# volume1882.net
KiCad netlist of a schematic drawn in EAGLE
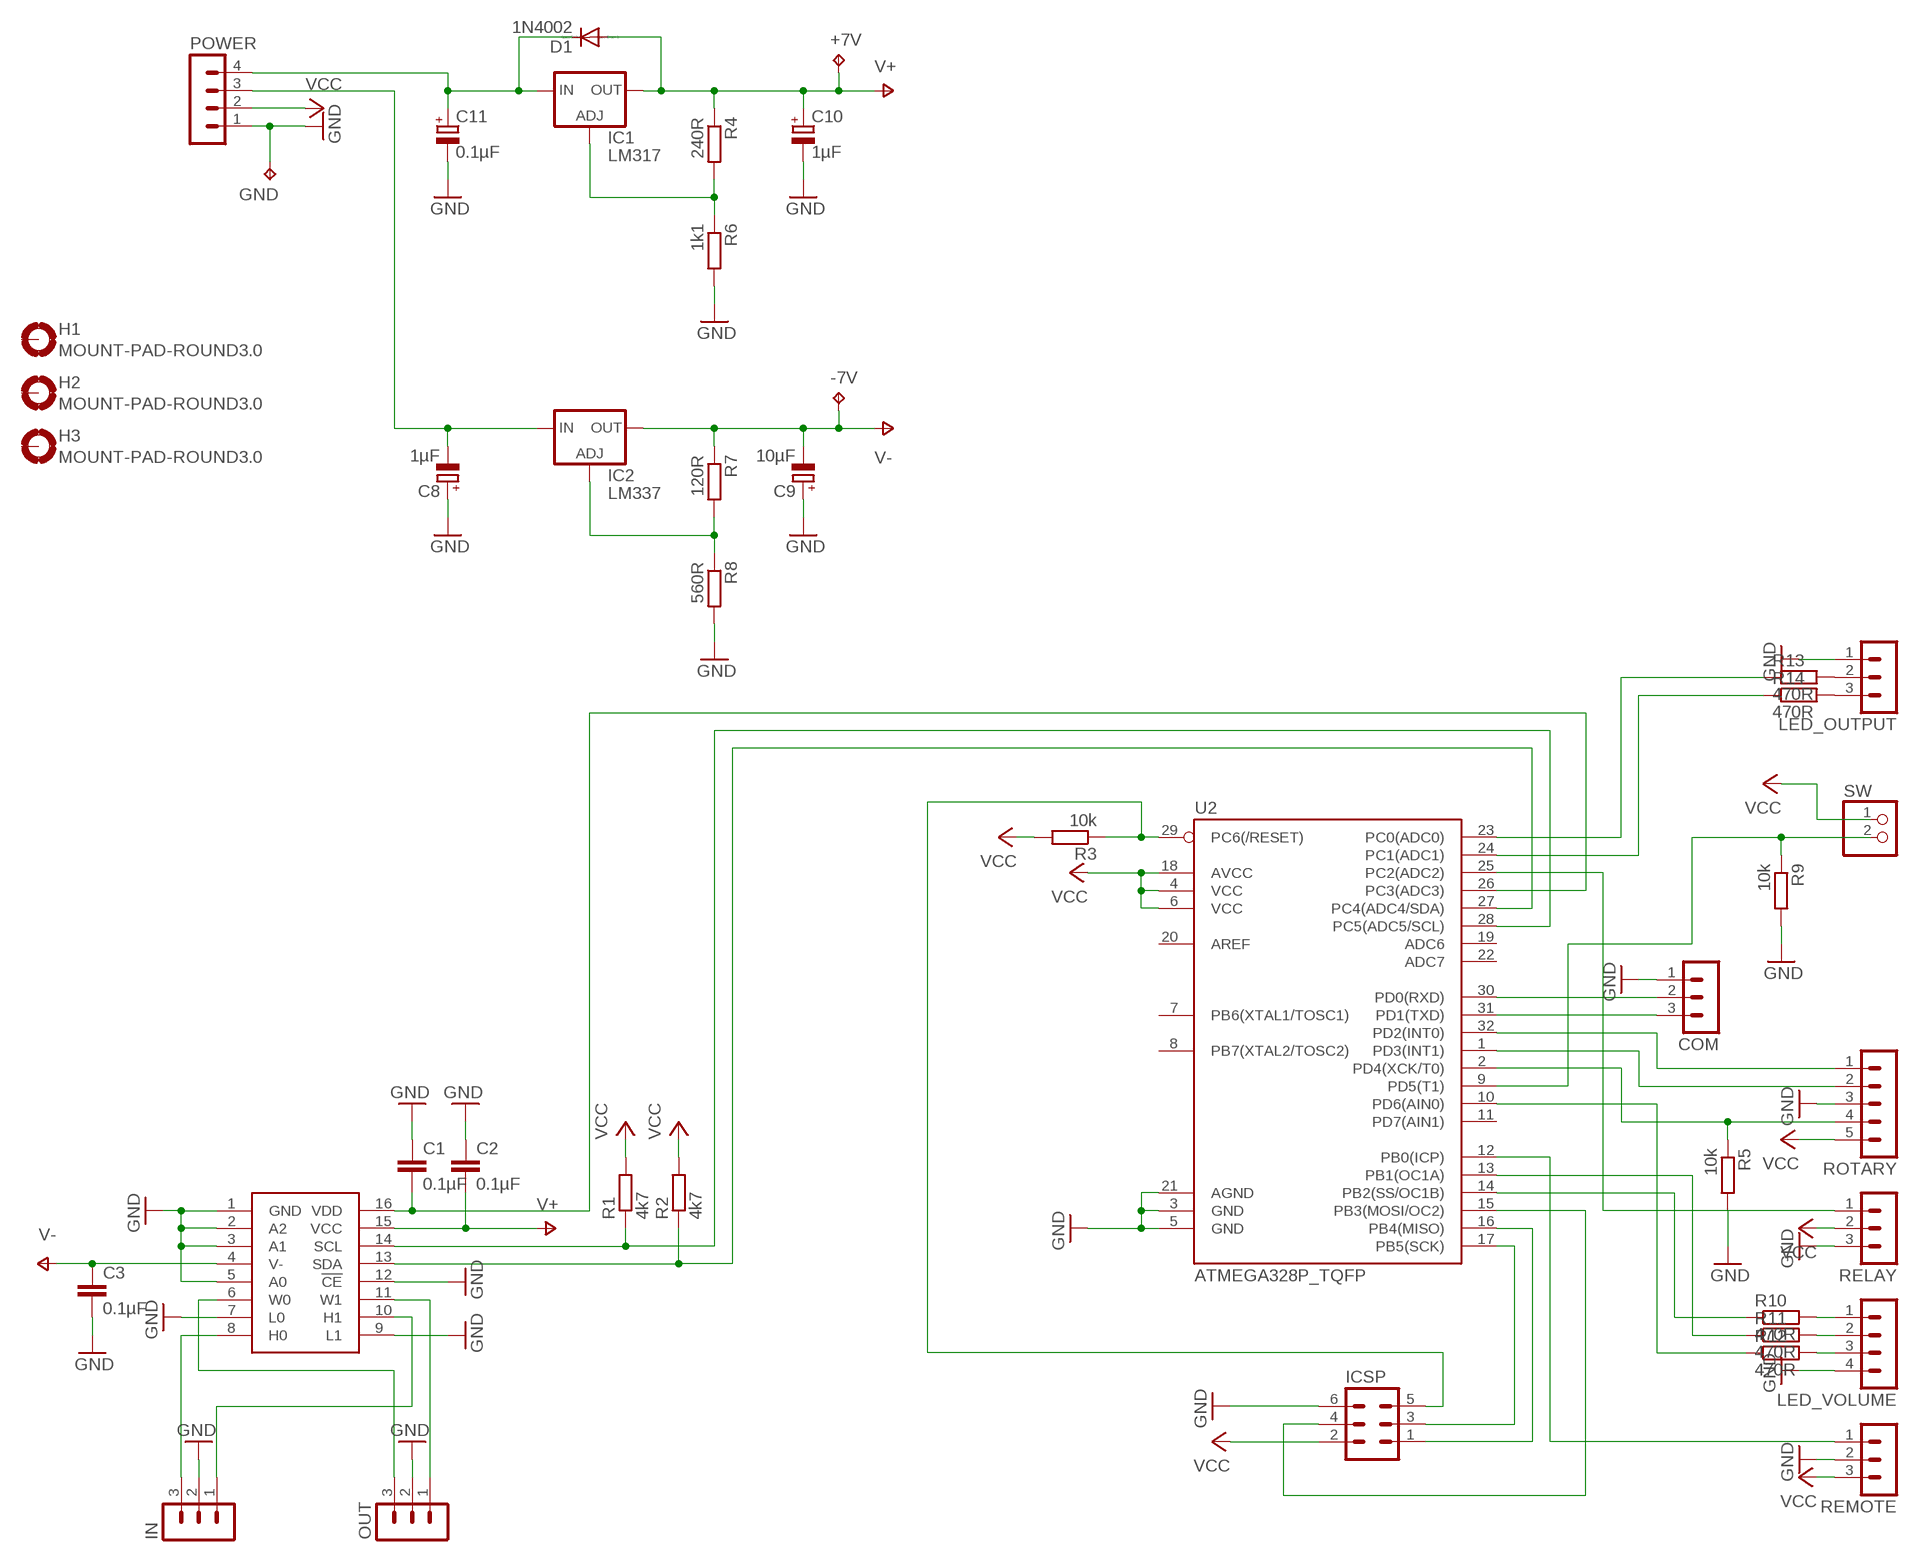
[diagram p0: schematic, sheet 1]

(export (version "E")
  (design (tool "Eeschema 10.0.6"))
  (components
    (comp (ref "+7V")
      (value "TPTP12SQ")
      (footprint "eagle-import:TP12SQ")
      (libsource (lib "eagle-import") (part "TPTP12SQ"))
    )
    (comp (ref "-7V")
      (value "TPTP12SQ")
      (footprint "eagle-import:TP12SQ")
      (libsource (lib "eagle-import") (part "TPTP12SQ"))
    )
    (comp (ref "C1")
      (value "0.1µF")
      (footprint "eagle-import:C1206")
      (libsource (lib "eagle-import") (part "C-EUC1206"))
    )
    (comp (ref "C2")
      (value "0.1µF")
      (footprint "eagle-import:C1206")
      (libsource (lib "eagle-import") (part "C-EUC1206"))
    )
    (comp (ref "C3")
      (value "0.1µF")
      (footprint "eagle-import:C1206")
      (libsource (lib "eagle-import") (part "C-EUC1206"))
    )
    (comp (ref "C8")
      (value "1µF")
      (footprint "eagle-import:E2-5")
      (libsource (lib "eagle-import") (part "CPOL-EUE2-5"))
    )
    (comp (ref "C9")
      (value "10µF")
      (footprint "eagle-import:E2-5")
      (libsource (lib "eagle-import") (part "CPOL-EUE2-5"))
    )
    (comp (ref "C10")
      (value "1µF")
      (footprint "eagle-import:E2-5")
      (libsource (lib "eagle-import") (part "CPOL-EUE2-5"))
    )
    (comp (ref "C11")
      (value "0.1µF")
      (footprint "eagle-import:E2-5")
      (libsource (lib "eagle-import") (part "CPOL-EUE2-5"))
    )
    (comp (ref "COM")
      (value "MA03-1")
      (footprint "eagle-import:MA03-1")
      (libsource (lib "eagle-import") (part "MA03-1"))
    )
    (comp (ref "D1")
      (value "1N4002")
      (footprint "eagle-import:DO41-10")
      (libsource (lib "eagle-import") (part "1N4004"))
    )
    (comp (ref "GND")
      (value "TPTP12SQ")
      (footprint "eagle-import:TP12SQ")
      (libsource (lib "eagle-import") (part "TPTP12SQ"))
    )
    (comp (ref "H1")
      (value "MOUNT-PAD-ROUND3.0")
      (footprint "eagle-import:3,0-PAD")
      (libsource (lib "eagle-import") (part "MOUNT-PAD-ROUND3.0"))
    )
    (comp (ref "H2")
      (value "MOUNT-PAD-ROUND3.0")
      (footprint "eagle-import:3,0-PAD")
      (libsource (lib "eagle-import") (part "MOUNT-PAD-ROUND3.0"))
    )
    (comp (ref "H3")
      (value "MOUNT-PAD-ROUND3.0")
      (footprint "eagle-import:3,0-PAD")
      (libsource (lib "eagle-import") (part "MOUNT-PAD-ROUND3.0"))
    )
    (comp (ref "IC1")
      (value "LM317")
      (footprint "eagle-import:SOT223")
      (libsource (lib "eagle-import") (part "LM317?MBSTT3"))
    )
    (comp (ref "IC2")
      (value "LM337")
      (footprint "eagle-import:SOT223")
      (libsource (lib "eagle-import") (part "LM337"))
    )
    (comp (ref "ICSP")
      (value "MA03-2")
      (footprint "eagle-import:MA03-2")
      (libsource (lib "eagle-import") (part "MA03-2"))
    )
    (comp (ref "IN")
      (value "MA03-1")
      (footprint "eagle-import:MA03-1")
      (libsource (lib "eagle-import") (part "MA03-1"))
    )
    (comp (ref "LED_OUTPUT")
      (value "MA03-1")
      (footprint "eagle-import:MA03-1")
      (libsource (lib "eagle-import") (part "MA03-1"))
    )
    (comp (ref "LED_VOLUME")
      (value "MA04-1")
      (footprint "eagle-import:MA04-1")
      (libsource (lib "eagle-import") (part "MA04-1"))
    )
    (comp (ref "OUT")
      (value "MA03-1")
      (footprint "eagle-import:MA03-1")
      (libsource (lib "eagle-import") (part "MA03-1"))
    )
    (comp (ref "POWER")
      (value "MA04-1")
      (footprint "eagle-import:MA04-1")
      (libsource (lib "eagle-import") (part "MA04-1"))
    )
    (comp (ref "R1")
      (value "4k7")
      (footprint "eagle-import:R1206")
      (libsource (lib "eagle-import") (part "R-EU_R1206"))
    )
    (comp (ref "R2")
      (value "4k7")
      (footprint "eagle-import:R1206")
      (libsource (lib "eagle-import") (part "R-EU_R1206"))
    )
    (comp (ref "R3")
      (value "10k")
      (footprint "eagle-import:R1206")
      (libsource (lib "eagle-import") (part "R-EU_R1206"))
    )
    (comp (ref "R4")
      (value "240R")
      (footprint "eagle-import:R1206")
      (libsource (lib "eagle-import") (part "R-EU_R1206"))
    )
    (comp (ref "R5")
      (value "10k")
      (footprint "eagle-import:R1206")
      (libsource (lib "eagle-import") (part "R-EU_R1206"))
    )
    (comp (ref "R6")
      (value "1k1")
      (footprint "eagle-import:R1206")
      (libsource (lib "eagle-import") (part "R-EU_R1206"))
    )
    (comp (ref "R7")
      (value "120R")
      (footprint "eagle-import:R1206")
      (libsource (lib "eagle-import") (part "R-EU_R1206"))
    )
    (comp (ref "R8")
      (value "560R")
      (footprint "eagle-import:R1206")
      (libsource (lib "eagle-import") (part "R-EU_R1206"))
    )
    (comp (ref "R9")
      (value "10k")
      (footprint "eagle-import:R1206")
      (libsource (lib "eagle-import") (part "R-EU_R1206"))
    )
    (comp (ref "R10")
      (value "470R")
      (footprint "eagle-import:R1206")
      (libsource (lib "eagle-import") (part "R-EU_R1206"))
    )
    (comp (ref "R11")
      (value "470R")
      (footprint "eagle-import:R1206")
      (libsource (lib "eagle-import") (part "R-EU_R1206"))
    )
    (comp (ref "R12")
      (value "470R")
      (footprint "eagle-import:R1206")
      (libsource (lib "eagle-import") (part "R-EU_R1206"))
    )
    (comp (ref "R13")
      (value "470R")
      (footprint "eagle-import:R1206")
      (libsource (lib "eagle-import") (part "R-EU_R1206"))
    )
    (comp (ref "R14")
      (value "470R")
      (footprint "eagle-import:R1206")
      (libsource (lib "eagle-import") (part "R-EU_R1206"))
    )
    (comp (ref "RELAY")
      (value "MA03-1")
      (footprint "eagle-import:MA03-1")
      (libsource (lib "eagle-import") (part "MA03-1"))
    )
    (comp (ref "REMOTE")
      (value "MA03-1")
      (footprint "eagle-import:MA03-1")
      (libsource (lib "eagle-import") (part "MA03-1"))
    )
    (comp (ref "ROTARY")
      (value "MA05-1")
      (footprint "eagle-import:MA05-1")
      (libsource (lib "eagle-import") (part "MA05-1"))
    )
    (comp (ref "SW")
      (value "PINHD-1X2")
      (footprint "eagle-import:1X02")
      (libsource (lib "eagle-import") (part "PINHD-1X2"))
    )
    (comp (ref "U1")
      (value "DS1882")
      (footprint "eagle-import:SO16")
      (libsource (lib "eagle-import") (part "DS1882"))
    )
    (comp (ref "U2")
      (value "ATMEGA328P_TQFP")
      (footprint "eagle-import:TQFP32-08")
      (libsource (lib "eagle-import") (part "ATMEGA328P_TQFP"))
    )
  )
  (nets
    (net (code "1") (name "GND") (class "Default")
      (node (ref "C1") (pin "1") (pinfunction "1_1") (pintype "passive"))
      (node (ref "C10") (pin "-") (pinfunction "-_-") (pintype "passive"))
      (node (ref "C11") (pin "-") (pinfunction "-_-") (pintype "passive"))
      (node (ref "C2") (pin "1") (pinfunction "1_1") (pintype "passive"))
      (node (ref "C3") (pin "2") (pinfunction "2_2") (pintype "passive"))
      (node (ref "C8") (pin "+") (pinfunction "+_+") (pintype "passive"))
      (node (ref "C9") (pin "+") (pinfunction "+_+") (pintype "passive"))
      (node (ref "COM") (pin "1") (pinfunction "1_1") (pintype "passive"))
      (node (ref "GND") (pin "TP") (pinfunction "TP_TP") (pintype "input"))
      (node (ref "ICSP") (pin "6") (pinfunction "6_6") (pintype "passive"))
      (node (ref "IN") (pin "2") (pinfunction "2_2") (pintype "passive"))
      (node (ref "LED_OUTPUT") (pin "1") (pinfunction "1_1") (pintype "passive"))
      (node (ref "LED_VOLUME") (pin "4") (pinfunction "4_4") (pintype "passive"))
      (node (ref "OUT") (pin "2") (pinfunction "2_2") (pintype "passive"))
      (node (ref "POWER") (pin "1") (pinfunction "1_1") (pintype "passive"))
      (node (ref "R5") (pin "2") (pinfunction "2_2") (pintype "passive"))
      (node (ref "R6") (pin "2") (pinfunction "2_2") (pintype "passive"))
      (node (ref "R8") (pin "2") (pinfunction "2_2") (pintype "passive"))
      (node (ref "R9") (pin "2") (pinfunction "2_2") (pintype "passive"))
      (node (ref "RELAY") (pin "3") (pinfunction "3_3") (pintype "passive"))
      (node (ref "REMOTE") (pin "2") (pinfunction "2_2") (pintype "passive"))
      (node (ref "ROTARY") (pin "3") (pinfunction "3_3") (pintype "passive"))
      (node (ref "U1") (pin "1") (pinfunction "GND_1") (pintype "power_in"))
      (node (ref "U1") (pin "12") (pinfunction "~{CE}_12") (pintype "bidirectional"))
      (node (ref "U1") (pin "2") (pinfunction "A2_2") (pintype "bidirectional"))
      (node (ref "U1") (pin "3") (pinfunction "A1_3") (pintype "bidirectional"))
      (node (ref "U1") (pin "5") (pinfunction "A0_5") (pintype "bidirectional"))
      (node (ref "U1") (pin "7") (pinfunction "L0_7") (pintype "bidirectional"))
      (node (ref "U1") (pin "9") (pinfunction "L1_9") (pintype "bidirectional"))
      (node (ref "U2") (pin "21") (pinfunction "AGND_21") (pintype "bidirectional"))
      (node (ref "U2") (pin "3") (pinfunction "GND_3") (pintype "bidirectional"))
      (node (ref "U2") (pin "5") (pinfunction "GND_5") (pintype "bidirectional"))
    )
    (net (code "2") (name "Net-(IC1-ADJ)") (class "Default")
      (node (ref "IC1") (pin "1") (pinfunction "ADJ_1") (pintype "input"))
      (node (ref "R4") (pin "2") (pinfunction "2_2") (pintype "passive"))
      (node (ref "R6") (pin "1") (pinfunction "1_1") (pintype "passive"))
    )
    (net (code "3") (name "Net-(IC1-IN)") (class "Default")
      (node (ref "C11") (pin "+") (pinfunction "+_+") (pintype "passive"))
      (node (ref "D1") (pin "C") (pinfunction "C_C") (pintype "passive"))
      (node (ref "IC1") (pin "3") (pinfunction "IN_3") (pintype "input"))
      (node (ref "POWER") (pin "4") (pinfunction "4_4") (pintype "passive"))
    )
    (net (code "4") (name "Net-(IC2-ADJ)") (class "Default")
      (node (ref "IC2") (pin "1") (pinfunction "ADJ_1") (pintype "input"))
      (node (ref "R7") (pin "2") (pinfunction "2_2") (pintype "passive"))
      (node (ref "R8") (pin "1") (pinfunction "1_1") (pintype "passive"))
    )
    (net (code "5") (name "Net-(IC2-IN)") (class "Default")
      (node (ref "C8") (pin "-") (pinfunction "-_-") (pintype "passive"))
      (node (ref "IC2") (pin "2") (pinfunction "IN_2") (pintype "input"))
      (node (ref "POWER") (pin "3") (pinfunction "3_3") (pintype "passive"))
    )
    (net (code "6") (name "Net-(LED_OUTPUT-Pad2)") (class "Default")
      (node (ref "LED_OUTPUT") (pin "2") (pinfunction "2_2") (pintype "passive"))
      (node (ref "R13") (pin "2") (pinfunction "2_2") (pintype "passive"))
    )
    (net (code "7") (name "Net-(LED_OUTPUT-Pad3)") (class "Default")
      (node (ref "LED_OUTPUT") (pin "3") (pinfunction "3_3") (pintype "passive"))
      (node (ref "R14") (pin "2") (pinfunction "2_2") (pintype "passive"))
    )
    (net (code "8") (name "Net-(LED_VOLUME-Pad1)") (class "Default")
      (node (ref "LED_VOLUME") (pin "1") (pinfunction "1_1") (pintype "passive"))
      (node (ref "R10") (pin "2") (pinfunction "2_2") (pintype "passive"))
    )
    (net (code "9") (name "Net-(LED_VOLUME-Pad2)") (class "Default")
      (node (ref "LED_VOLUME") (pin "2") (pinfunction "2_2") (pintype "passive"))
      (node (ref "R11") (pin "2") (pinfunction "2_2") (pintype "passive"))
    )
    (net (code "10") (name "Net-(LED_VOLUME-Pad3)") (class "Default")
      (node (ref "LED_VOLUME") (pin "3") (pinfunction "3_3") (pintype "passive"))
      (node (ref "R12") (pin "2") (pinfunction "2_2") (pintype "passive"))
    )
    (net (code "11") (name "Net-(U1-H0)") (class "Default")
      (node (ref "IN") (pin "3") (pinfunction "3_3") (pintype "passive"))
      (node (ref "U1") (pin "8") (pinfunction "H0_8") (pintype "bidirectional"))
    )
    (net (code "12") (name "Net-(U1-H1)") (class "Default")
      (node (ref "IN") (pin "1") (pinfunction "1_1") (pintype "passive"))
      (node (ref "U1") (pin "10") (pinfunction "H1_10") (pintype "bidirectional"))
    )
    (net (code "13") (name "Net-(U1-SCL)") (class "Default")
      (node (ref "R1") (pin "1") (pinfunction "1_1") (pintype "passive"))
      (node (ref "U1") (pin "14") (pinfunction "SCL_14") (pintype "bidirectional"))
      (node (ref "U2") (pin "28") (pinfunction "PC5(ADC5/SCL)_28") (pintype "bidirectional"))
    )
    (net (code "14") (name "Net-(U1-SDA)") (class "Default")
      (node (ref "R2") (pin "1") (pinfunction "1_1") (pintype "passive"))
      (node (ref "U1") (pin "13") (pinfunction "SDA_13") (pintype "bidirectional"))
      (node (ref "U2") (pin "27") (pinfunction "PC4(ADC4/SDA)_27") (pintype "bidirectional"))
    )
    (net (code "15") (name "Net-(U1-VDD)") (class "Default")
      (node (ref "C1") (pin "2") (pinfunction "2_2") (pintype "passive"))
      (node (ref "U1") (pin "16") (pinfunction "VDD_16") (pintype "power_in"))
      (node (ref "U2") (pin "26") (pinfunction "PC3(ADC3)_26") (pintype "bidirectional"))
    )
    (net (code "16") (name "Net-(U1-W0)") (class "Default")
      (node (ref "OUT") (pin "3") (pinfunction "3_3") (pintype "passive"))
      (node (ref "U1") (pin "6") (pinfunction "W0_6") (pintype "bidirectional"))
    )
    (net (code "17") (name "Net-(U1-W1)") (class "Default")
      (node (ref "OUT") (pin "1") (pinfunction "1_1") (pintype "passive"))
      (node (ref "U1") (pin "11") (pinfunction "W1_11") (pintype "bidirectional"))
    )
    (net (code "18") (name "Net-(U2-PB0(ICP))") (class "Default")
      (node (ref "REMOTE") (pin "1") (pinfunction "1_1") (pintype "passive"))
      (node (ref "U2") (pin "12") (pinfunction "PB0(ICP)_12") (pintype "bidirectional"))
    )
    (net (code "19") (name "Net-(U2-PB1(OC1A))") (class "Default")
      (node (ref "R11") (pin "1") (pinfunction "1_1") (pintype "passive"))
      (node (ref "U2") (pin "13") (pinfunction "PB1(OC1A)_13") (pintype "bidirectional"))
    )
    (net (code "20") (name "Net-(U2-PB2(SS{slash}OC1B))") (class "Default")
      (node (ref "R10") (pin "1") (pinfunction "1_1") (pintype "passive"))
      (node (ref "U2") (pin "14") (pinfunction "PB2(SS/OC1B)_14") (pintype "bidirectional"))
    )
    (net (code "21") (name "Net-(U2-PB3(MOSI{slash}OC2))") (class "Default")
      (node (ref "ICSP") (pin "4") (pinfunction "4_4") (pintype "passive"))
      (node (ref "U2") (pin "15") (pinfunction "PB3(MOSI/OC2)_15") (pintype "bidirectional"))
    )
    (net (code "22") (name "Net-(U2-PB4(MISO))") (class "Default")
      (node (ref "ICSP") (pin "1") (pinfunction "1_1") (pintype "passive"))
      (node (ref "U2") (pin "16") (pinfunction "PB4(MISO)_16") (pintype "bidirectional"))
    )
    (net (code "23") (name "Net-(U2-PB5(SCK))") (class "Default")
      (node (ref "ICSP") (pin "3") (pinfunction "3_3") (pintype "passive"))
      (node (ref "U2") (pin "17") (pinfunction "PB5(SCK)_17") (pintype "bidirectional"))
    )
    (net (code "24") (name "Net-(U2-PC0(ADC0))") (class "Default")
      (node (ref "R13") (pin "1") (pinfunction "1_1") (pintype "passive"))
      (node (ref "U2") (pin "23") (pinfunction "PC0(ADC0)_23") (pintype "bidirectional"))
    )
    (net (code "25") (name "Net-(U2-PC1(ADC1))") (class "Default")
      (node (ref "R14") (pin "1") (pinfunction "1_1") (pintype "passive"))
      (node (ref "U2") (pin "24") (pinfunction "PC1(ADC1)_24") (pintype "bidirectional"))
    )
    (net (code "26") (name "Net-(U2-PC2(ADC2))") (class "Default")
      (node (ref "RELAY") (pin "1") (pinfunction "1_1") (pintype "passive"))
      (node (ref "U2") (pin "25") (pinfunction "PC2(ADC2)_25") (pintype "bidirectional"))
    )
    (net (code "27") (name "Net-(U2-PC6({slash}RESET))") (class "Default")
      (node (ref "ICSP") (pin "5") (pinfunction "5_5") (pintype "passive"))
      (node (ref "R3") (pin "1") (pinfunction "1_1") (pintype "passive"))
      (node (ref "U2") (pin "29") (pinfunction "PC6(/RESET)_29") (pintype "bidirectional"))
    )
    (net (code "28") (name "Net-(U2-PD0(RXD))") (class "Default")
      (node (ref "COM") (pin "2") (pinfunction "2_2") (pintype "passive"))
      (node (ref "U2") (pin "30") (pinfunction "PD0(RXD)_30") (pintype "bidirectional"))
    )
    (net (code "29") (name "Net-(U2-PD1(TXD))") (class "Default")
      (node (ref "COM") (pin "3") (pinfunction "3_3") (pintype "passive"))
      (node (ref "U2") (pin "31") (pinfunction "PD1(TXD)_31") (pintype "bidirectional"))
    )
    (net (code "30") (name "Net-(U2-PD2(INT0))") (class "Default")
      (node (ref "ROTARY") (pin "1") (pinfunction "1_1") (pintype "passive"))
      (node (ref "U2") (pin "32") (pinfunction "PD2(INT0)_32") (pintype "bidirectional"))
    )
    (net (code "31") (name "Net-(U2-PD3(INT1))") (class "Default")
      (node (ref "ROTARY") (pin "2") (pinfunction "2_2") (pintype "passive"))
      (node (ref "U2") (pin "1") (pinfunction "PD3(INT1)_1") (pintype "bidirectional"))
    )
    (net (code "32") (name "Net-(U2-PD4(XCK{slash}T0))") (class "Default")
      (node (ref "R5") (pin "1") (pinfunction "1_1") (pintype "passive"))
      (node (ref "ROTARY") (pin "4") (pinfunction "4_4") (pintype "passive"))
      (node (ref "U2") (pin "2") (pinfunction "PD4(XCK/T0)_2") (pintype "bidirectional"))
    )
    (net (code "33") (name "Net-(U2-PD5(T1))") (class "Default")
      (node (ref "R9") (pin "1") (pinfunction "1_1") (pintype "passive"))
      (node (ref "SW") (pin "2") (pinfunction "2_2") (pintype "passive"))
      (node (ref "U2") (pin "9") (pinfunction "PD5(T1)_9") (pintype "bidirectional"))
    )
    (net (code "34") (name "Net-(U2-PD6(AIN0))") (class "Default")
      (node (ref "R12") (pin "1") (pinfunction "1_1") (pintype "passive"))
      (node (ref "U2") (pin "10") (pinfunction "PD6(AIN0)_10") (pintype "bidirectional"))
    )
    (net (code "35") (name "V+") (class "Default")
      (node (ref "+7V") (pin "TP") (pinfunction "TP_TP") (pintype "input"))
      (node (ref "C10") (pin "+") (pinfunction "+_+") (pintype "passive"))
      (node (ref "C2") (pin "2") (pinfunction "2_2") (pintype "passive"))
      (node (ref "D1") (pin "A") (pinfunction "A_A") (pintype "passive"))
      (node (ref "IC1") (pin "4") (pinfunction "OUT_4") (pintype "passive"))
      (node (ref "R4") (pin "1") (pinfunction "1_1") (pintype "passive"))
      (node (ref "U1") (pin "15") (pinfunction "VCC_15") (pintype "power_in"))
    )
    (net (code "36") (name "V-") (class "Default")
      (node (ref "-7V") (pin "TP") (pinfunction "TP_TP") (pintype "input"))
      (node (ref "C3") (pin "1") (pinfunction "1_1") (pintype "passive"))
      (node (ref "C9") (pin "-") (pinfunction "-_-") (pintype "passive"))
      (node (ref "IC2") (pin "3") (pinfunction "OUT_3") (pintype "passive"))
      (node (ref "R7") (pin "1") (pinfunction "1_1") (pintype "passive"))
      (node (ref "U1") (pin "4") (pinfunction "V-_4") (pintype "power_in"))
    )
    (net (code "37") (name "VCC") (class "Default")
      (node (ref "ICSP") (pin "2") (pinfunction "2_2") (pintype "passive"))
      (node (ref "POWER") (pin "2") (pinfunction "2_2") (pintype "passive"))
      (node (ref "R1") (pin "2") (pinfunction "2_2") (pintype "passive"))
      (node (ref "R2") (pin "2") (pinfunction "2_2") (pintype "passive"))
      (node (ref "R3") (pin "2") (pinfunction "2_2") (pintype "passive"))
      (node (ref "RELAY") (pin "2") (pinfunction "2_2") (pintype "passive"))
      (node (ref "REMOTE") (pin "3") (pinfunction "3_3") (pintype "passive"))
      (node (ref "ROTARY") (pin "5") (pinfunction "5_5") (pintype "passive"))
      (node (ref "SW") (pin "1") (pinfunction "1_1") (pintype "passive"))
      (node (ref "U2") (pin "18") (pinfunction "AVCC_18") (pintype "bidirectional"))
      (node (ref "U2") (pin "4") (pinfunction "VCC_4") (pintype "bidirectional"))
      (node (ref "U2") (pin "6") (pinfunction "VCC_6") (pintype "bidirectional"))
    )
    (net (code "38") (name "unconnected-(H1-MOUNT-PadB3,0)") (class "Default")
      (node (ref "H1") (pin "B3,0") (pinfunction "MOUNT_B3,0") (pintype "passive"))
    )
    (net (code "39") (name "unconnected-(H2-MOUNT-PadB3,0)") (class "Default")
      (node (ref "H2") (pin "B3,0") (pinfunction "MOUNT_B3,0") (pintype "passive"))
    )
    (net (code "40") (name "unconnected-(H3-MOUNT-PadB3,0)") (class "Default")
      (node (ref "H3") (pin "B3,0") (pinfunction "MOUNT_B3,0") (pintype "passive"))
    )
    (net (code "41") (name "unconnected-(U2-ADC6-Pad19)") (class "Default")
      (node (ref "U2") (pin "19") (pinfunction "ADC6_19") (pintype "bidirectional"))
    )
    (net (code "42") (name "unconnected-(U2-ADC7-Pad22)") (class "Default")
      (node (ref "U2") (pin "22") (pinfunction "ADC7_22") (pintype "bidirectional"))
    )
    (net (code "43") (name "unconnected-(U2-AREF-Pad20)") (class "Default")
      (node (ref "U2") (pin "20") (pinfunction "AREF_20") (pintype "bidirectional"))
    )
    (net (code "44") (name "unconnected-(U2-PB6(XTAL1{slash}TOSC1)-Pad7)") (class "Default")
      (node (ref "U2") (pin "7") (pinfunction "PB6(XTAL1/TOSC1)_7") (pintype "bidirectional"))
    )
    (net (code "45") (name "unconnected-(U2-PB7(XTAL2{slash}TOSC2)-Pad8)") (class "Default")
      (node (ref "U2") (pin "8") (pinfunction "PB7(XTAL2/TOSC2)_8") (pintype "bidirectional"))
    )
    (net (code "46") (name "unconnected-(U2-PD7(AIN1)-Pad11)") (class "Default")
      (node (ref "U2") (pin "11") (pinfunction "PD7(AIN1)_11") (pintype "bidirectional"))
    )
  )
)
